# PlatineOben.net
KiCad netlist of a schematic drawn in EAGLE
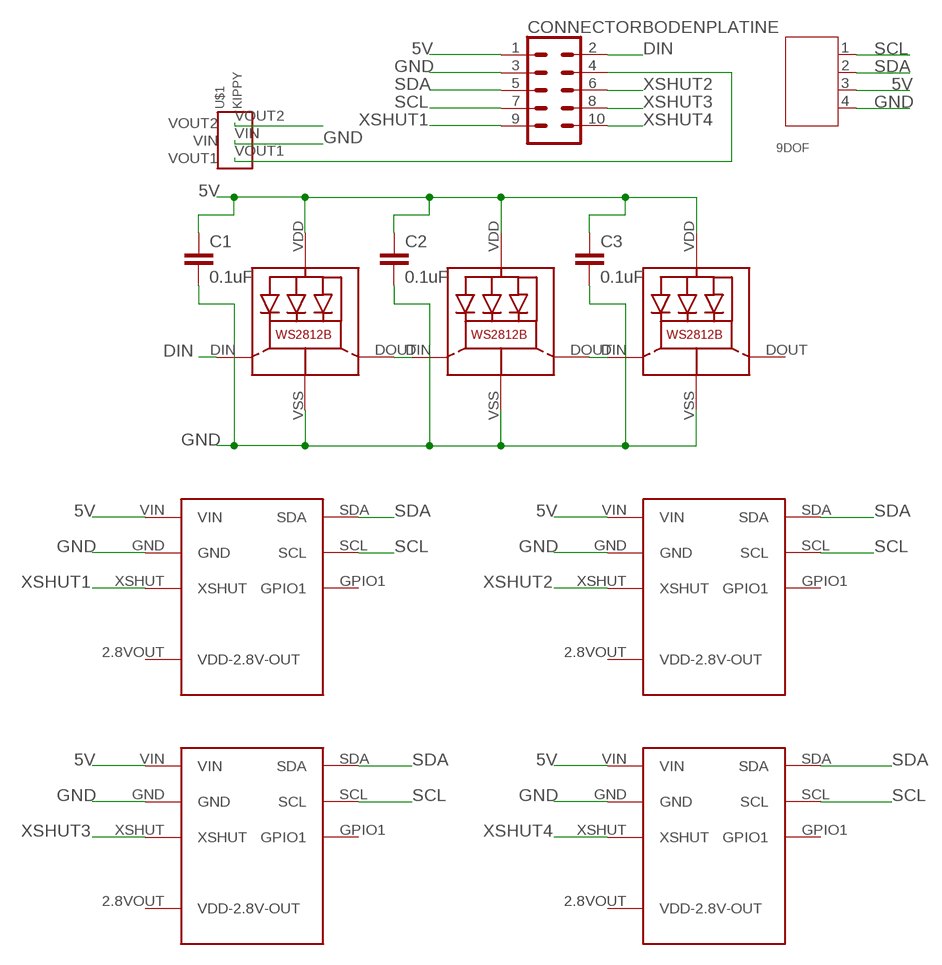
[diagram p0: schematic, sheet 1]

(export (version "E")
  (design (tool "Eeschema 10.0.6"))
  (components
    (comp (ref "9DOF")
      (value "4P-2.0")
      (footprint "eagle-import:JST-PH4")
      (libsource (lib "eagle-import") (part "JST-PH4"))
    )
    (comp (ref "C1")
      (value "0.1uF")
      (footprint "eagle-import:C0805")
      (libsource (lib "eagle-import") (part "C-EUC0805"))
    )
    (comp (ref "C2")
      (value "0.1uF")
      (footprint "eagle-import:C0805")
      (libsource (lib "eagle-import") (part "C-EUC0805"))
    )
    (comp (ref "C3")
      (value "0.1uF")
      (footprint "eagle-import:C0805")
      (libsource (lib "eagle-import") (part "C-EUC0805"))
    )
    (comp (ref "CONNECTORBODENPLATINE")
      (value "CONN_05X2")
      (footprint "eagle-import:2X5-SHROUDED(3D)")
      (libsource (lib "eagle-import") (part "CONN_05X2"))
    )
    (comp (ref "LED1")
      (value "WS2812B")
      (footprint "eagle-import:WS2812B")
      (libsource (lib "eagle-import") (part "WS2812B"))
    )
    (comp (ref "LED2")
      (value "WS2812B")
      (footprint "eagle-import:WS2812B")
      (libsource (lib "eagle-import") (part "WS2812B"))
    )
    (comp (ref "LED3")
      (value "WS2812B")
      (footprint "eagle-import:WS2812B")
      (libsource (lib "eagle-import") (part "WS2812B"))
    )
    (comp (ref "TOFH")
      (value "TOFPOLOLUSTEHEND")
      (footprint "eagle-import:TOFPOLOLU_STEHEND")
      (libsource (lib "eagle-import") (part "TOFPOLOLUSTEHEND"))
    )
    (comp (ref "TOFL")
      (value "TOFPOLOLUSTEHEND")
      (footprint "eagle-import:TOFPOLOLU_STEHEND")
      (libsource (lib "eagle-import") (part "TOFPOLOLUSTEHEND"))
    )
    (comp (ref "TOFR")
      (value "TOFPOLOLUSTEHEND")
      (footprint "eagle-import:TOFPOLOLU_STEHEND")
      (libsource (lib "eagle-import") (part "TOFPOLOLUSTEHEND"))
    )
    (comp (ref "TOFV")
      (value "TOFPOLOLUSTEHEND")
      (footprint "eagle-import:TOFPOLOLU_STEHEND")
      (libsource (lib "eagle-import") (part "TOFPOLOLUSTEHEND"))
    )
    (comp (ref "U$1")
      (value "KIPPY")
      (footprint "eagle-import:KIPPY")
      (libsource (lib "eagle-import") (part "KIPPY"))
    )
  )
  (nets
    (net (code "1") (name "/5V") (class "Default")
      (node (ref "9DOF") (pin "3") (pinfunction "3_3") (pintype "passive"))
      (node (ref "C1") (pin "1") (pinfunction "1_1") (pintype "passive"))
      (node (ref "C2") (pin "1") (pinfunction "1_1") (pintype "passive"))
      (node (ref "C3") (pin "1") (pinfunction "1_1") (pintype "passive"))
      (node (ref "CONNECTORBODENPLATINE") (pin "1") (pinfunction "1_1") (pintype "passive"))
      (node (ref "LED1") (pin "VDD") (pinfunction "VDD_VDD") (pintype "power_in"))
      (node (ref "LED2") (pin "VDD") (pinfunction "VDD_VDD") (pintype "power_in"))
      (node (ref "LED3") (pin "VDD") (pinfunction "VDD_VDD") (pintype "power_in"))
      (node (ref "TOFH") (pin "VIN") (pinfunction "VIN_VIN") (pintype "bidirectional"))
      (node (ref "TOFL") (pin "VIN") (pinfunction "VIN_VIN") (pintype "bidirectional"))
      (node (ref "TOFR") (pin "VIN") (pinfunction "VIN_VIN") (pintype "bidirectional"))
      (node (ref "TOFV") (pin "VIN") (pinfunction "VIN_VIN") (pintype "bidirectional"))
    )
    (net (code "2") (name "/DIN") (class "Default")
      (node (ref "CONNECTORBODENPLATINE") (pin "2") (pinfunction "2_2") (pintype "passive"))
      (node (ref "LED1") (pin "DIN") (pinfunction "DI_DIN") (pintype "input"))
    )
    (net (code "3") (name "/GND") (class "Default")
      (node (ref "9DOF") (pin "4") (pinfunction "4_4") (pintype "passive"))
      (node (ref "C1") (pin "2") (pinfunction "2_2") (pintype "passive"))
      (node (ref "C2") (pin "2") (pinfunction "2_2") (pintype "passive"))
      (node (ref "C3") (pin "2") (pinfunction "2_2") (pintype "passive"))
      (node (ref "CONNECTORBODENPLATINE") (pin "3") (pinfunction "3_3") (pintype "passive"))
      (node (ref "LED1") (pin "VSS") (pinfunction "GND_VSS") (pintype "power_in"))
      (node (ref "LED2") (pin "VSS") (pinfunction "GND_VSS") (pintype "power_in"))
      (node (ref "LED3") (pin "VSS") (pinfunction "GND_VSS") (pintype "power_in"))
      (node (ref "TOFH") (pin "GND") (pinfunction "GND_GND") (pintype "bidirectional"))
      (node (ref "TOFL") (pin "GND") (pinfunction "GND_GND") (pintype "bidirectional"))
      (node (ref "TOFR") (pin "GND") (pinfunction "GND_GND") (pintype "bidirectional"))
      (node (ref "TOFV") (pin "GND") (pinfunction "GND_GND") (pintype "bidirectional"))
      (node (ref "U$1") (pin "VIN") (pinfunction "VIN_VIN") (pintype "input"))
    )
    (net (code "4") (name "/SCL") (class "Default")
      (node (ref "9DOF") (pin "1") (pinfunction "1_1") (pintype "passive"))
      (node (ref "CONNECTORBODENPLATINE") (pin "7") (pinfunction "7_7") (pintype "passive"))
      (node (ref "TOFH") (pin "SCL") (pinfunction "SCL_SCL") (pintype "bidirectional"))
      (node (ref "TOFL") (pin "SCL") (pinfunction "SCL_SCL") (pintype "bidirectional"))
      (node (ref "TOFR") (pin "SCL") (pinfunction "SCL_SCL") (pintype "bidirectional"))
      (node (ref "TOFV") (pin "SCL") (pinfunction "SCL_SCL") (pintype "bidirectional"))
    )
    (net (code "5") (name "/SDA") (class "Default")
      (node (ref "9DOF") (pin "2") (pinfunction "2_2") (pintype "passive"))
      (node (ref "CONNECTORBODENPLATINE") (pin "5") (pinfunction "5_5") (pintype "passive"))
      (node (ref "TOFH") (pin "SDA") (pinfunction "SDA_SDA") (pintype "bidirectional"))
      (node (ref "TOFL") (pin "SDA") (pinfunction "SDA_SDA") (pintype "bidirectional"))
      (node (ref "TOFR") (pin "SDA") (pinfunction "SDA_SDA") (pintype "bidirectional"))
      (node (ref "TOFV") (pin "SDA") (pinfunction "SDA_SDA") (pintype "bidirectional"))
    )
    (net (code "6") (name "/XSHUT1") (class "Default")
      (node (ref "CONNECTORBODENPLATINE") (pin "9") (pinfunction "9_9") (pintype "passive"))
      (node (ref "TOFR") (pin "XSHUT") (pinfunction "XSHUT_XSHUT") (pintype "bidirectional"))
    )
    (net (code "7") (name "/XSHUT2") (class "Default")
      (node (ref "CONNECTORBODENPLATINE") (pin "6") (pinfunction "6_6") (pintype "passive"))
      (node (ref "TOFL") (pin "XSHUT") (pinfunction "XSHUT_XSHUT") (pintype "bidirectional"))
    )
    (net (code "8") (name "/XSHUT3") (class "Default")
      (node (ref "CONNECTORBODENPLATINE") (pin "8") (pinfunction "8_8") (pintype "passive"))
      (node (ref "TOFV") (pin "XSHUT") (pinfunction "XSHUT_XSHUT") (pintype "bidirectional"))
    )
    (net (code "9") (name "/XSHUT4") (class "Default")
      (node (ref "CONNECTORBODENPLATINE") (pin "10") (pinfunction "10_10") (pintype "passive"))
      (node (ref "TOFH") (pin "XSHUT") (pinfunction "XSHUT_XSHUT") (pintype "bidirectional"))
    )
    (net (code "10") (name "Net-(CONNECTORBODENPLATINE-Pad4)") (class "Default")
      (node (ref "CONNECTORBODENPLATINE") (pin "4") (pinfunction "4_4") (pintype "passive"))
      (node (ref "U$1") (pin "VOUT1") (pinfunction "VOUT1_VOUT1") (pintype "output"))
    )
    (net (code "11") (name "Net-(LED1-DO)") (class "Default")
      (node (ref "LED1") (pin "DOUT") (pinfunction "DO_DOUT") (pintype "output"))
      (node (ref "LED2") (pin "DIN") (pinfunction "DI_DIN") (pintype "input"))
    )
    (net (code "12") (name "Net-(LED2-DO)") (class "Default")
      (node (ref "LED2") (pin "DOUT") (pinfunction "DO_DOUT") (pintype "output"))
      (node (ref "LED3") (pin "DIN") (pinfunction "DI_DIN") (pintype "input"))
    )
    (net (code "13") (name "unconnected-(LED3-DO-PadDOUT)") (class "Default")
      (node (ref "LED3") (pin "DOUT") (pinfunction "DO_DOUT") (pintype "output"))
    )
    (net (code "14") (name "unconnected-(TOFH-PadGPIO1)") (class "Default")
      (node (ref "TOFH") (pin "GPIO1") (pinfunction "GPIO1_GPIO1") (pintype "bidirectional"))
    )
    (net (code "15") (name "unconnected-(TOFH-VDD-2.8V-OUT-Pad2.8VOUT)") (class "Default")
      (node (ref "TOFH") (pin "2.8VOUT") (pinfunction "VDD-2.8V-OUT_2.8VOUT") (pintype "bidirectional"))
    )
    (net (code "16") (name "unconnected-(TOFL-PadGPIO1)") (class "Default")
      (node (ref "TOFL") (pin "GPIO1") (pinfunction "GPIO1_GPIO1") (pintype "bidirectional"))
    )
    (net (code "17") (name "unconnected-(TOFL-VDD-2.8V-OUT-Pad2.8VOUT)") (class "Default")
      (node (ref "TOFL") (pin "2.8VOUT") (pinfunction "VDD-2.8V-OUT_2.8VOUT") (pintype "bidirectional"))
    )
    (net (code "18") (name "unconnected-(TOFR-PadGPIO1)") (class "Default")
      (node (ref "TOFR") (pin "GPIO1") (pinfunction "GPIO1_GPIO1") (pintype "bidirectional"))
    )
    (net (code "19") (name "unconnected-(TOFR-VDD-2.8V-OUT-Pad2.8VOUT)") (class "Default")
      (node (ref "TOFR") (pin "2.8VOUT") (pinfunction "VDD-2.8V-OUT_2.8VOUT") (pintype "bidirectional"))
    )
    (net (code "20") (name "unconnected-(TOFV-PadGPIO1)") (class "Default")
      (node (ref "TOFV") (pin "GPIO1") (pinfunction "GPIO1_GPIO1") (pintype "bidirectional"))
    )
    (net (code "21") (name "unconnected-(TOFV-VDD-2.8V-OUT-Pad2.8VOUT)") (class "Default")
      (node (ref "TOFV") (pin "2.8VOUT") (pinfunction "VDD-2.8V-OUT_2.8VOUT") (pintype "bidirectional"))
    )
    (net (code "22") (name "unconnected-(U$1-PadVOUT2)") (class "Default")
      (node (ref "U$1") (pin "VOUT2") (pinfunction "VOUT2_VOUT2") (pintype "output"))
    )
  )
)
